# SRD_Generator_scheme.net
KiCad netlist of a schematic drawn in Altium Designer
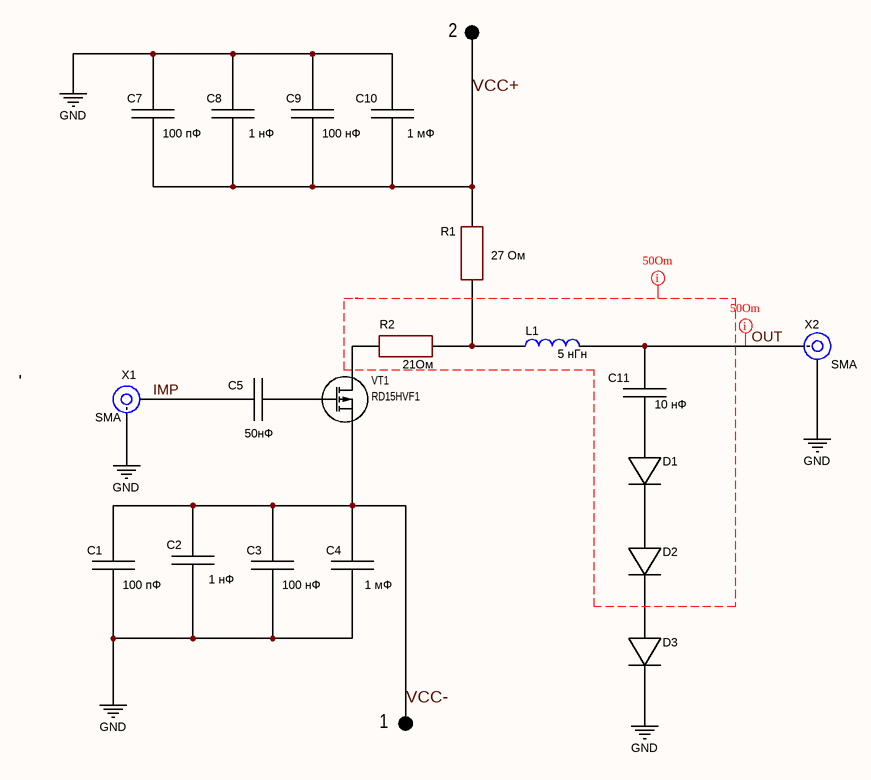
[diagram p0: SRD Generator scheme.SchDoc]

(export (version "E")
  (design (tool "Eeschema 10.0.6"))
  (components
    (comp (ref "1")
      (value "SMD, 1.5x1.5mm")
      (footprint "Test point Rectan SMD")
      (fields (field (name "PART NUMBER") "Test point Rectan SMD"))
      (libsource (lib "DB_AltiumDesigner") (part "Test Point"))
    )
    (comp (ref "2")
      (value "SMD, 1.5x1.5mm")
      (footprint "Test point Rectan SMD")
      (fields (field (name "PART NUMBER") "Test point Rectan SMD"))
      (libsource (lib "DB_AltiumDesigner") (part "Test Point"))
    )
    (comp (ref "C1")
      (value "100 пФ")
      (footprint "CH0603C")
      (libsource (lib "SRD Generator") (part "Capacitor"))
    )
    (comp (ref "C2")
      (value "1 нФ")
      (footprint "CH0603C")
      (libsource (lib "SRD Generator") (part "Capacitor"))
    )
    (comp (ref "C3")
      (value "100 нФ")
      (footprint "CH0603C")
      (libsource (lib "SRD Generator") (part "Capacitor"))
    )
    (comp (ref "C4")
      (value "1 мФ")
      (footprint "CH0603C")
      (libsource (lib "SRD Generator") (part "Capacitor"))
    )
    (comp (ref "C5")
      (value "50нФ")
      (footprint "CH0603C")
      (libsource (lib "SRD Generator") (part "Capacitor_1"))
    )
    (comp (ref "C7")
      (value "100 пФ")
      (footprint "CH0603C")
      (libsource (lib "SRD Generator") (part "Capacitor"))
    )
    (comp (ref "C8")
      (value "1 нФ")
      (footprint "CH0603C")
      (libsource (lib "SRD Generator") (part "Capacitor"))
    )
    (comp (ref "C9")
      (value "100 нФ")
      (footprint "CH0603C")
      (libsource (lib "SRD Generator") (part "Capacitor"))
    )
    (comp (ref "C10")
      (value "1 мФ")
      (footprint "CH0603C")
      (libsource (lib "SRD Generator") (part "Capacitor"))
    )
    (comp (ref "C11")
      (value "10 нФ")
      (footprint "CH0603C")
      (libsource (lib "SRD Generator") (part "Capacitor"))
    )
    (comp (ref "D1")
      (value "SRD")
      (footprint "Diode Macom")
      (description "https://ru.mouser.com/datasheet/2/249/maom_s_a0004987266_1-2274246.pdf")
      (libsource (lib "SRD Generator") (part "SRD"))
    )
    (comp (ref "D2")
      (value "SRD")
      (footprint "Diode Macom")
      (description "https://ru.mouser.com/datasheet/2/249/maom_s_a0004987266_1-2274246.pdf")
      (libsource (lib "SRD Generator") (part "SRD"))
    )
    (comp (ref "D3")
      (value "SRD")
      (footprint "Diode Macom")
      (description "https://ru.mouser.com/datasheet/2/249/maom_s_a0004987266_1-2274246.pdf")
      (libsource (lib "SRD Generator") (part "SRD"))
    )
    (comp (ref "L1")
      (value "5 нГн")
      (footprint "0402-A")
      (description "Inductor")
      (fields (field (name "PUBLISHER") "Altium Limited"))
      (libsource (lib "Miscellaneous Devices") (part "Inductor"))
    )
    (comp (ref "R1") (value "27 Ом") (footprint "R2512") (libsource (lib "SRD Generator") (part "Resistor")))
    (comp (ref "R2")
      (value "21Ом")
      (footprint "CH0603R")
      (libsource (lib "SRD Generator") (part "Resistor_1"))
    )
    (comp (ref "VT1")
      (value "RD15HVF1")
      (footprint "TO220_123")
      (description "Mosfet")
      (libsource (lib "SRD Generator") (part "P-chanel -diod"))
    )
    (comp (ref "X1")
      (value "SMA")
      (footprint "SMA-90deg")
      (description "RF")
      (libsource (lib "") (part "SMA_1"))
    )
    (comp (ref "X2")
      (value "SMA")
      (footprint "SMA-90deg")
      (description "RF")
      (libsource (lib "SRD Generator") (part "SMA"))
    )
  )
  (nets
    (net (code "1") (name "/IMP") (class "Default")
      (node (ref "C5") (pin "1") (pinfunction "1_1") (pintype "power_in"))
      (node (ref "X1") (pin "1") (pinfunction "IN_1") (pintype "passive"))
    )
    (net (code "2") (name "/OUT") (class "Default")
      (node (ref "C11") (pin "2") (pinfunction "2_2") (pintype "power_in"))
      (node (ref "L1") (pin "2") (pinfunction "2_2") (pintype "passive"))
      (node (ref "X2") (pin "1") (pinfunction "IN_1") (pintype "passive"))
    )
    (net (code "3") (name "/VCC+") (class "Default")
      (node (ref "2") (pin "1") (pinfunction "1_1") (pintype "passive"))
      (node (ref "C10") (pin "1") (pinfunction "1_1") (pintype "power_in"))
      (node (ref "C7") (pin "1") (pinfunction "1_1") (pintype "power_in"))
      (node (ref "C8") (pin "1") (pinfunction "1_1") (pintype "power_in"))
      (node (ref "C9") (pin "1") (pinfunction "1_1") (pintype "power_in"))
      (node (ref "R1") (pin "2") (pinfunction "2_2") (pintype "passive"))
    )
    (net (code "4") (name "/VCC-") (class "Default")
      (node (ref "1") (pin "1") (pinfunction "1_1") (pintype "passive"))
      (node (ref "C1") (pin "2") (pinfunction "2_2") (pintype "power_in"))
      (node (ref "C2") (pin "2") (pinfunction "2_2") (pintype "power_in"))
      (node (ref "C3") (pin "2") (pinfunction "2_2") (pintype "power_in"))
      (node (ref "C4") (pin "2") (pinfunction "2_2") (pintype "power_in"))
      (node (ref "VT1") (pin "3") (pinfunction "S_3") (pintype "passive"))
    )
    (net (code "5") (name "GND") (class "Default")
      (node (ref "C1") (pin "1") (pinfunction "1_1") (pintype "power_in"))
      (node (ref "C10") (pin "2") (pinfunction "2_2") (pintype "power_in"))
      (node (ref "C2") (pin "1") (pinfunction "1_1") (pintype "power_in"))
      (node (ref "C3") (pin "1") (pinfunction "1_1") (pintype "power_in"))
      (node (ref "C4") (pin "1") (pinfunction "1_1") (pintype "power_in"))
      (node (ref "C7") (pin "2") (pinfunction "2_2") (pintype "power_in"))
      (node (ref "C8") (pin "2") (pinfunction "2_2") (pintype "power_in"))
      (node (ref "C9") (pin "2") (pinfunction "2_2") (pintype "power_in"))
      (node (ref "D3") (pin "2") (pinfunction "К_2") (pintype "passive"))
      (node (ref "X1") (pin "2") (pinfunction "IN_2") (pintype "passive"))
      (node (ref "X2") (pin "2") (pinfunction "IN_2") (pintype "passive"))
    )
    (net (code "6") (name "Net-(D1-A)") (class "Default")
      (node (ref "C11") (pin "1") (pinfunction "1_1") (pintype "power_in"))
      (node (ref "D1") (pin "1") (pinfunction "A_1") (pintype "passive"))
    )
    (net (code "7") (name "Net-(D1-К)") (class "Default")
      (node (ref "D1") (pin "2") (pinfunction "К_2") (pintype "passive"))
      (node (ref "D2") (pin "1") (pinfunction "A_1") (pintype "passive"))
    )
    (net (code "8") (name "Net-(D2-К)") (class "Default")
      (node (ref "D2") (pin "2") (pinfunction "К_2") (pintype "passive"))
      (node (ref "D3") (pin "1") (pinfunction "A_1") (pintype "passive"))
    )
    (net (code "9") (name "Net-(L1-Pad1)") (class "Default")
      (node (ref "L1") (pin "1") (pinfunction "1_1") (pintype "passive"))
      (node (ref "R1") (pin "1") (pinfunction "1_1") (pintype "passive"))
      (node (ref "R2") (pin "1") (pinfunction "1_1") (pintype "passive"))
    )
    (net (code "10") (name "Net-(VT1-D)") (class "Default")
      (node (ref "R2") (pin "2") (pinfunction "2_2") (pintype "passive"))
      (node (ref "VT1") (pin "2") (pinfunction "D_2") (pintype "passive"))
    )
    (net (code "11") (name "Net-(VT1-G)") (class "Default")
      (node (ref "C5") (pin "2") (pinfunction "2_2") (pintype "power_in"))
      (node (ref "VT1") (pin "1") (pinfunction "G_1") (pintype "passive"))
    )
  )
)
